# ElectricalLoads.net
KiCad netlist of a schematic drawn in EAGLE
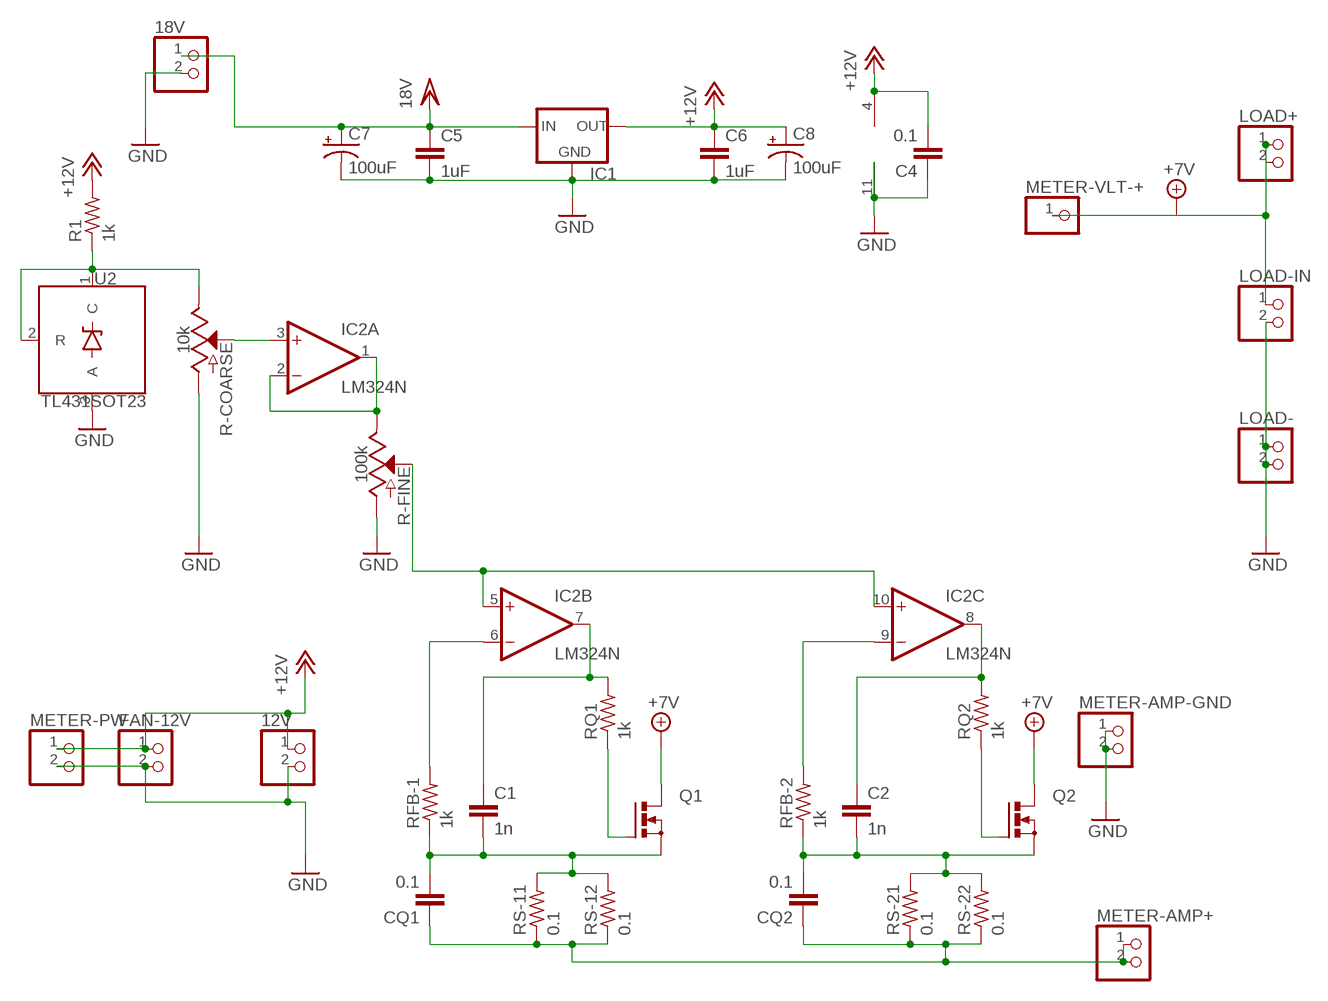
[diagram p0: schematic, sheet 1]

(export (version "E")
  (design (tool "Eeschema 10.0.6"))
  (components
    (comp (ref "12V")
      (value "PINHD-1X2")
      (footprint "eagle-import:1X02")
      (libsource (lib "eagle-import") (part "PINHD-1X2"))
    )
    (comp (ref "18V")
      (value "PINHD-1X2")
      (footprint "eagle-import:1X02")
      (libsource (lib "eagle-import") (part "PINHD-1X2"))
    )
    (comp (ref "C1")
      (value "1n")
      (footprint "eagle-import:0805")
      (libsource (lib "eagle-import") (part "CAP-0805"))
    )
    (comp (ref "C2")
      (value "1n")
      (footprint "eagle-import:0805")
      (libsource (lib "eagle-import") (part "CAP-0805"))
    )
    (comp (ref "C4")
      (value "0.1")
      (footprint "eagle-import:0805")
      (libsource (lib "eagle-import") (part "CAP-0805"))
    )
    (comp (ref "C5")
      (value "1uF")
      (footprint "eagle-import:1210")
      (libsource (lib "eagle-import") (part "10UF-1210-50V-20%"))
    )
    (comp (ref "C6")
      (value "1uF")
      (footprint "eagle-import:1210")
      (libsource (lib "eagle-import") (part "10UF-1210-50V-20%"))
    )
    (comp (ref "C7")
      (value "100uF")
      (footprint "eagle-import:PANASONIC_D")
      (libsource (lib "eagle-import") (part "100UF-POLAR-25V-20%(ELEC)"))
    )
    (comp (ref "C8")
      (value "100uF")
      (footprint "eagle-import:PANASONIC_D")
      (libsource (lib "eagle-import") (part "100UF-POLAR-25V-20%(ELEC)"))
    )
    (comp (ref "CQ1")
      (value "0.1")
      (footprint "eagle-import:0805")
      (libsource (lib "eagle-import") (part "CAP-0805"))
    )
    (comp (ref "CQ2")
      (value "0.1")
      (footprint "eagle-import:0805")
      (libsource (lib "eagle-import") (part "CAP-0805"))
    )
    (comp (ref "FAN-12V")
      (value "PINHD-1X2")
      (footprint "eagle-import:1X02")
      (libsource (lib "eagle-import") (part "PINHD-1X2"))
    )
    (comp (ref "IC1")
      (value "78XXS")
      (footprint "eagle-import:78XXS")
      (libsource (lib "eagle-import") (part "78XXS"))
    )
    (comp (ref "IC2")
      (value "LM324N")
      (footprint "eagle-import:DIL14")
      (libsource (lib "eagle-import") (part "LM324N"))
    )
    (comp (ref "LOAD+")
      (value "PINHD-1X2")
      (footprint "eagle-import:1X02")
      (libsource (lib "eagle-import") (part "PINHD-1X2"))
    )
    (comp (ref "LOAD-")
      (value "PINHD-1X2")
      (footprint "eagle-import:1X02")
      (libsource (lib "eagle-import") (part "PINHD-1X2"))
    )
    (comp (ref "LOAD-IN")
      (value "PINHD-1X2")
      (footprint "eagle-import:1X02")
      (libsource (lib "eagle-import") (part "PINHD-1X2"))
    )
    (comp (ref "METER-AMP+")
      (value "PINHD-1X2")
      (footprint "eagle-import:1X02")
      (libsource (lib "eagle-import") (part "PINHD-1X2"))
    )
    (comp (ref "METER-AMP-GND")
      (value "PINHD-1X2")
      (footprint "eagle-import:1X02")
      (libsource (lib "eagle-import") (part "PINHD-1X2"))
    )
    (comp (ref "METER-PW")
      (value "PINHD-1X2")
      (footprint "eagle-import:1X02")
      (libsource (lib "eagle-import") (part "PINHD-1X2"))
    )
    (comp (ref "METER-VLT-+")
      (value "PINHD-1X1")
      (footprint "eagle-import:1X01")
      (libsource (lib "eagle-import") (part "PINHD-1X1"))
    )
    (comp (ref "Q1")
      (value "PMOSFET_NTO220BH")
      (footprint "eagle-import:TO220BH")
      (libsource (lib "eagle-import") (part "PMOSFET_NTO220BH"))
    )
    (comp (ref "Q2")
      (value "PMOSFET_NTO220BH")
      (footprint "eagle-import:TO220BH")
      (libsource (lib "eagle-import") (part "PMOSFET_NTO220BH"))
    )
    (comp (ref "R-COARSE")
      (value "10k")
      (footprint "eagle-import:POT-PTH-ALPS")
      (libsource (lib "eagle-import") (part "POTENTIOMETER-PTH-9MM-1/20W-20%"))
    )
    (comp (ref "R-FINE")
      (value "100k")
      (footprint "eagle-import:POT-PTH-ALPS")
      (libsource (lib "eagle-import") (part "POTENTIOMETER-PTH-9MM-1/20W-20%"))
    )
    (comp (ref "R1")
      (value "1k")
      (footprint "eagle-import:M0805")
      (libsource (lib "eagle-import") (part "R-US_M0805"))
    )
    (comp (ref "RFB-1")
      (value "1k")
      (footprint "eagle-import:M0805")
      (libsource (lib "eagle-import") (part "R-US_M0805"))
    )
    (comp (ref "RFB-2")
      (value "1k")
      (footprint "eagle-import:M0805")
      (libsource (lib "eagle-import") (part "R-US_M0805"))
    )
    (comp (ref "RQ1")
      (value "1k")
      (footprint "eagle-import:M0805")
      (libsource (lib "eagle-import") (part "R-US_M0805"))
    )
    (comp (ref "RQ2")
      (value "1k")
      (footprint "eagle-import:M0805")
      (libsource (lib "eagle-import") (part "R-US_M0805"))
    )
    (comp (ref "RS-11")
      (value "0.1")
      (footprint "eagle-import:R2512")
      (libsource (lib "eagle-import") (part "R-US_R2512"))
    )
    (comp (ref "RS-12")
      (value "0.1")
      (footprint "eagle-import:R2512")
      (libsource (lib "eagle-import") (part "R-US_R2512"))
    )
    (comp (ref "RS-21")
      (value "0.1")
      (footprint "eagle-import:R2512")
      (libsource (lib "eagle-import") (part "R-US_R2512"))
    )
    (comp (ref "RS-22")
      (value "0.1")
      (footprint "eagle-import:R2512")
      (libsource (lib "eagle-import") (part "R-US_R2512"))
    )
    (comp (ref "U2")
      (value "TL431SOT23")
      (footprint "eagle-import:SOT23-3")
      (libsource (lib "eagle-import") (part "TL431SOT23"))
    )
  )
  (nets
    (net (code "1") (name "+7V") (class "Default")
      (node (ref "LOAD+") (pin "1") (pinfunction "1_1") (pintype "passive"))
      (node (ref "LOAD+") (pin "2") (pinfunction "2_2") (pintype "passive"))
      (node (ref "LOAD-IN") (pin "1") (pinfunction "1_1") (pintype "passive"))
      (node (ref "METER-VLT-+") (pin "1") (pinfunction "1_1") (pintype "passive"))
      (node (ref "Q1") (pin "D") (pinfunction "D_D") (pintype "passive"))
      (node (ref "Q2") (pin "D") (pinfunction "D_D") (pintype "passive"))
    )
    (net (code "2") (name "+12V") (class "Default")
      (node (ref "12V") (pin "1") (pinfunction "1_1") (pintype "passive"))
      (node (ref "C4") (pin "2") (pinfunction "2_2") (pintype "passive"))
      (node (ref "C6") (pin "1") (pinfunction "1_1") (pintype "passive"))
      (node (ref "C8") (pin "+") (pinfunction "+_+") (pintype "passive"))
      (node (ref "FAN-12V") (pin "1") (pinfunction "1_1") (pintype "passive"))
      (node (ref "IC1") (pin "OUT") (pinfunction "OUT_OUT") (pintype "passive"))
      (node (ref "IC2") (pin "4") (pinfunction "V+_4") (pintype "power_in"))
      (node (ref "METER-PW") (pin "1") (pinfunction "1_1") (pintype "passive"))
      (node (ref "R1") (pin "2") (pinfunction "2_2") (pintype "passive"))
    )
    (net (code "3") (name "18V") (class "Default")
      (node (ref "18V") (pin "1") (pinfunction "1_1") (pintype "passive"))
      (node (ref "C5") (pin "1") (pinfunction "1_1") (pintype "passive"))
      (node (ref "C7") (pin "+") (pinfunction "+_+") (pintype "passive"))
      (node (ref "IC1") (pin "IN") (pinfunction "IN_IN") (pintype "input"))
    )
    (net (code "4") (name "GND") (class "Default")
      (node (ref "12V") (pin "2") (pinfunction "2_2") (pintype "passive"))
      (node (ref "18V") (pin "2") (pinfunction "2_2") (pintype "passive"))
      (node (ref "C4") (pin "1") (pinfunction "1_1") (pintype "passive"))
      (node (ref "C5") (pin "2") (pinfunction "2_2") (pintype "passive"))
      (node (ref "C6") (pin "2") (pinfunction "2_2") (pintype "passive"))
      (node (ref "C7") (pin "-") (pinfunction "-_-") (pintype "passive"))
      (node (ref "C8") (pin "-") (pinfunction "-_-") (pintype "passive"))
      (node (ref "FAN-12V") (pin "2") (pinfunction "2_2") (pintype "passive"))
      (node (ref "IC1") (pin "GND") (pinfunction "GND_GND") (pintype "input"))
      (node (ref "IC2") (pin "11") (pinfunction "V-_11") (pintype "power_in"))
      (node (ref "LOAD-") (pin "1") (pinfunction "1_1") (pintype "passive"))
      (node (ref "LOAD-") (pin "2") (pinfunction "2_2") (pintype "passive"))
      (node (ref "LOAD-IN") (pin "2") (pinfunction "2_2") (pintype "passive"))
      (node (ref "METER-AMP-GND") (pin "1") (pinfunction "1_1") (pintype "passive"))
      (node (ref "METER-AMP-GND") (pin "2") (pinfunction "2_2") (pintype "passive"))
      (node (ref "METER-PW") (pin "2") (pinfunction "2_2") (pintype "passive"))
      (node (ref "R-COARSE") (pin "P$3") (pinfunction "A_P$3") (pintype "passive"))
      (node (ref "R-FINE") (pin "P$3") (pinfunction "A_P$3") (pintype "passive"))
      (node (ref "U2") (pin "3") (pinfunction "A_3") (pintype "bidirectional"))
    )
    (net (code "5") (name "Net-(C1-Pad2)") (class "Default")
      (node (ref "C1") (pin "2") (pinfunction "2_2") (pintype "passive"))
      (node (ref "CQ1") (pin "2") (pinfunction "2_2") (pintype "passive"))
      (node (ref "Q1") (pin "S") (pinfunction "S_S") (pintype "passive"))
      (node (ref "RFB-1") (pin "1") (pinfunction "1_1") (pintype "passive"))
      (node (ref "RS-11") (pin "2") (pinfunction "2_2") (pintype "passive"))
      (node (ref "RS-12") (pin "2") (pinfunction "2_2") (pintype "passive"))
    )
    (net (code "6") (name "Net-(C2-Pad2)") (class "Default")
      (node (ref "C2") (pin "2") (pinfunction "2_2") (pintype "passive"))
      (node (ref "CQ2") (pin "2") (pinfunction "2_2") (pintype "passive"))
      (node (ref "Q2") (pin "S") (pinfunction "S_S") (pintype "passive"))
      (node (ref "RFB-2") (pin "1") (pinfunction "1_1") (pintype "passive"))
      (node (ref "RS-21") (pin "2") (pinfunction "2_2") (pintype "passive"))
      (node (ref "RS-22") (pin "2") (pinfunction "2_2") (pintype "passive"))
    )
    (net (code "7") (name "Net-(CQ1-Pad1)") (class "Default")
      (node (ref "CQ1") (pin "1") (pinfunction "1_1") (pintype "passive"))
      (node (ref "CQ2") (pin "1") (pinfunction "1_1") (pintype "passive"))
      (node (ref "METER-AMP+") (pin "1") (pinfunction "1_1") (pintype "passive"))
      (node (ref "METER-AMP+") (pin "2") (pinfunction "2_2") (pintype "passive"))
      (node (ref "RS-11") (pin "1") (pinfunction "1_1") (pintype "passive"))
      (node (ref "RS-12") (pin "1") (pinfunction "1_1") (pintype "passive"))
      (node (ref "RS-21") (pin "1") (pinfunction "1_1") (pintype "passive"))
      (node (ref "RS-22") (pin "1") (pinfunction "1_1") (pintype "passive"))
    )
    (net (code "8") (name "Net-(IC2A-+IN)") (class "Default")
      (node (ref "IC2") (pin "3") (pinfunction "+IN_3") (pintype "input"))
      (node (ref "R-COARSE") (pin "P$2") (pinfunction "S_P$2") (pintype "passive"))
    )
    (net (code "9") (name "Net-(IC2A--IN)") (class "Default")
      (node (ref "IC2") (pin "1") (pinfunction "OUT_1") (pintype "output"))
      (node (ref "IC2") (pin "2") (pinfunction "-IN_2") (pintype "input"))
      (node (ref "R-FINE") (pin "P$1") (pinfunction "E_P$1") (pintype "passive"))
    )
    (net (code "10") (name "Net-(IC2B-+IN)") (class "Default")
      (node (ref "IC2") (pin "10") (pinfunction "+IN_10") (pintype "input"))
      (node (ref "IC2") (pin "5") (pinfunction "+IN_5") (pintype "input"))
      (node (ref "R-FINE") (pin "P$2") (pinfunction "S_P$2") (pintype "passive"))
    )
    (net (code "11") (name "Net-(IC2B--IN)") (class "Default")
      (node (ref "IC2") (pin "6") (pinfunction "-IN_6") (pintype "input"))
      (node (ref "RFB-1") (pin "2") (pinfunction "2_2") (pintype "passive"))
    )
    (net (code "12") (name "Net-(IC2B-OUT)") (class "Default")
      (node (ref "C1") (pin "1") (pinfunction "1_1") (pintype "passive"))
      (node (ref "IC2") (pin "7") (pinfunction "OUT_7") (pintype "output"))
      (node (ref "RQ1") (pin "2") (pinfunction "2_2") (pintype "passive"))
    )
    (net (code "13") (name "Net-(IC2C--IN)") (class "Default")
      (node (ref "IC2") (pin "9") (pinfunction "-IN_9") (pintype "input"))
      (node (ref "RFB-2") (pin "2") (pinfunction "2_2") (pintype "passive"))
    )
    (net (code "14") (name "Net-(IC2C-OUT)") (class "Default")
      (node (ref "C2") (pin "1") (pinfunction "1_1") (pintype "passive"))
      (node (ref "IC2") (pin "8") (pinfunction "OUT_8") (pintype "output"))
      (node (ref "RQ2") (pin "2") (pinfunction "2_2") (pintype "passive"))
    )
    (net (code "15") (name "Net-(Q1-PadG)") (class "Default")
      (node (ref "Q1") (pin "G") (pinfunction "G_G") (pintype "passive"))
      (node (ref "RQ1") (pin "1") (pinfunction "1_1") (pintype "passive"))
    )
    (net (code "16") (name "Net-(Q2-PadG)") (class "Default")
      (node (ref "Q2") (pin "G") (pinfunction "G_G") (pintype "passive"))
      (node (ref "RQ2") (pin "1") (pinfunction "1_1") (pintype "passive"))
    )
    (net (code "17") (name "Net-(R-COARSE-E)") (class "Default")
      (node (ref "R-COARSE") (pin "P$1") (pinfunction "E_P$1") (pintype "passive"))
      (node (ref "R1") (pin "1") (pinfunction "1_1") (pintype "passive"))
      (node (ref "U2") (pin "1") (pinfunction "C_1") (pintype "bidirectional"))
      (node (ref "U2") (pin "2") (pinfunction "R_2") (pintype "bidirectional"))
    )
  )
)
